# Schematic_Daughter_Board.net
KiCad netlist of a schematic drawn in Altium Designer
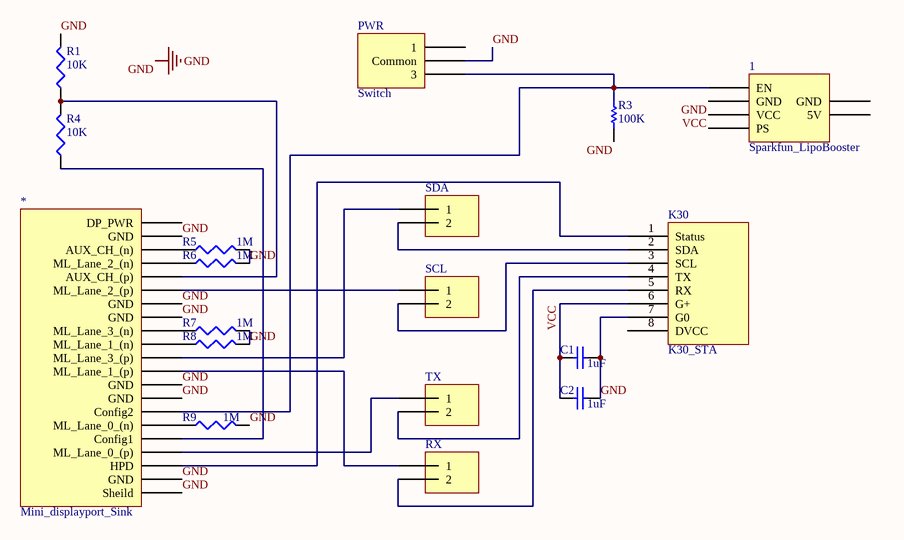
[diagram p0: Schematic_Daughter_Board.SchDoc]

(export (version "E")
  (design (tool "Eeschema 10.0.6"))
  (components
    (comp (ref "*")
      (value "Mini_displayport_Sink")
      (footprint "CONN_Displayport")
      (libsource (lib "Parts_Schematic") (part "Mini_displayport_Sink"))
    )
    (comp (ref "1")
      (value "Sparkfun_LipoBooster")
      (footprint "Sparkfun_lipoBooster")
      (libsource (lib "Schematic_Library_DaughterBoard") (part "Sparkfun_LipoBooster"))
    )
    (comp (ref "C1")
      (value "1uF")
      (footprint "C0805")
      (description "Capacitor (Semiconductor SIM Model)")
      (fields (field (name "Comment") "Cap Semi") (field (name "PUBLISHER") "Altium Limited"))
      (libsource (lib "Miscellaneous Devices") (part "Cap Semi"))
    )
    (comp (ref "C2")
      (value "1uF")
      (footprint "C0805")
      (description "Capacitor (Semiconductor SIM Model)")
      (fields (field (name "Comment") "Cap Semi") (field (name "PUBLISHER") "Altium Limited"))
      (libsource (lib "Miscellaneous Devices") (part "Cap Semi"))
    )
    (comp (ref "K30")
      (value "K30_STA")
      (footprint "K30_STA")
      (libsource (lib "Schematic_Library_DaughterBoard") (part "K30_STA"))
    )
    (comp (ref "PWR")
      (value "Switch")
      (footprint "Switch_footprint")
      (libsource (lib "Parts_Schematic") (part "Switch"))
    )
    (comp (ref "R1")
      (value "10K")
      (footprint "6-0805_N")
      (description "Resistor")
      (fields (field (name "Comment") "Res3") (field (name "PUBLISHER") "Altium Limited"))
      (libsource (lib "Miscellaneous Devices") (part "Res3"))
    )
    (comp (ref "R3")
      (value "100K")
      (footprint "AXIAL-0.3")
      (description "Resistor")
      (fields (field (name "Comment") "Res1") (field (name "PUBLISHER") "Altium Limited"))
      (libsource (lib "Miscellaneous Devices") (part "Res1"))
    )
    (comp (ref "R4")
      (value "10K")
      (footprint "6-0805_N")
      (description "Resistor")
      (fields (field (name "Comment") "Res3") (field (name "PUBLISHER") "Altium Limited"))
      (libsource (lib "Miscellaneous Devices") (part "Res3"))
    )
    (comp (ref "R5")
      (value "1M")
      (footprint "6-0805_N")
      (description "Resistor")
      (fields (field (name "Comment") "Res3") (field (name "PUBLISHER") "Altium Limited"))
      (libsource (lib "Miscellaneous Devices") (part "Res3"))
    )
    (comp (ref "R6")
      (value "1M")
      (footprint "6-0805_N")
      (description "Resistor")
      (fields (field (name "Comment") "Res3") (field (name "PUBLISHER") "Altium Limited"))
      (libsource (lib "Miscellaneous Devices") (part "Res3"))
    )
    (comp (ref "R7")
      (value "1M")
      (footprint "6-0805_N")
      (description "Resistor")
      (fields (field (name "Comment") "Res3") (field (name "PUBLISHER") "Altium Limited"))
      (libsource (lib "Miscellaneous Devices") (part "Res3"))
    )
    (comp (ref "R8")
      (value "1M")
      (footprint "6-0805_N")
      (description "Resistor")
      (fields (field (name "Comment") "Res3") (field (name "PUBLISHER") "Altium Limited"))
      (libsource (lib "Miscellaneous Devices") (part "Res3"))
    )
    (comp (ref "R9")
      (value "1M")
      (footprint "6-0805_N")
      (description "Resistor")
      (fields (field (name "Comment") "Res3") (field (name "PUBLISHER") "Altium Limited"))
      (libsource (lib "Miscellaneous Devices") (part "Res3"))
    )
    (comp (ref "RX")
      (value "Solder_Jumper")
      (footprint "Solder_Jumper_Footprint")
      (libsource (lib "Schematic_Library_DaughterBoard") (part "Solder_Jumper"))
    )
    (comp (ref "SCL")
      (value "Solder_Jumper")
      (footprint "Solder_Jumper_Footprint")
      (libsource (lib "Schematic_Library_DaughterBoard") (part "Solder_Jumper"))
    )
    (comp (ref "SDA")
      (value "Solder_Jumper")
      (footprint "Solder_Jumper_Footprint")
      (libsource (lib "Schematic_Library_DaughterBoard") (part "Solder_Jumper"))
    )
    (comp (ref "TX")
      (value "Solder_Jumper")
      (footprint "Solder_Jumper_Footprint")
      (libsource (lib "Schematic_Library_DaughterBoard") (part "Solder_Jumper"))
    )
  )
  (nets
    (net (code "1") (name "/VCC") (class "Default")
      (node (ref "1") (pin "3") (pinfunction "VCC_3") (pintype "passive"))
      (node (ref "C1") (pin "2") (pinfunction "2_2") (pintype "passive"))
      (node (ref "C2") (pin "2") (pinfunction "2_2") (pintype "passive"))
      (node (ref "K30") (pin "6") (pinfunction "G+_6") (pintype "passive"))
    )
    (net (code "2") (name "GND") (class "Default")
      (node (ref "*") (pin "0") (pinfunction "Sheild_0") (pintype "passive"))
      (node (ref "*") (pin "1") (pinfunction "GND_1") (pintype "passive"))
      (node (ref "*") (pin "13") (pinfunction "GND_13") (pintype "passive"))
      (node (ref "*") (pin "14") (pinfunction "GND_14") (pintype "passive"))
      (node (ref "*") (pin "19") (pinfunction "GND_19") (pintype "passive"))
      (node (ref "*") (pin "7") (pinfunction "GND_7") (pintype "passive"))
      (node (ref "*") (pin "8") (pinfunction "GND_8") (pintype "passive"))
      (node (ref "1") (pin "2") (pinfunction "GND_2") (pintype "passive"))
      (node (ref "C1") (pin "1") (pinfunction "1_1") (pintype "passive"))
      (node (ref "C2") (pin "1") (pinfunction "1_1") (pintype "passive"))
      (node (ref "K30") (pin "7") (pinfunction "G0_7") (pintype "passive"))
      (node (ref "PWR") (pin "2") (pinfunction "Common_2") (pintype "passive"))
      (node (ref "R1") (pin "2") (pinfunction "2_2") (pintype "passive"))
      (node (ref "R3") (pin "1") (pinfunction "1_1") (pintype "passive"))
      (node (ref "R5") (pin "2") (pinfunction "2_2") (pintype "passive"))
      (node (ref "R6") (pin "2") (pinfunction "2_2") (pintype "passive"))
      (node (ref "R7") (pin "2") (pinfunction "2_2") (pintype "passive"))
      (node (ref "R8") (pin "2") (pinfunction "2_2") (pintype "passive"))
      (node (ref "R9") (pin "2") (pinfunction "2_2") (pintype "passive"))
    )
    (net (code "3") (name "Net-(*-AUX_CH_(n))") (class "Default")
      (node (ref "*") (pin "18") (pinfunction "AUX_CH_(n)_18") (pintype "passive"))
      (node (ref "R5") (pin "1") (pinfunction "1_1") (pintype "passive"))
    )
    (net (code "4") (name "Net-(*-AUX_CH_(p))") (class "Default")
      (node (ref "*") (pin "16") (pinfunction "AUX_CH_(p)_16") (pintype "passive"))
      (node (ref "R1") (pin "1") (pinfunction "1_1") (pintype "passive"))
      (node (ref "R4") (pin "2") (pinfunction "2_2") (pintype "passive"))
    )
    (net (code "5") (name "Net-(*-Config1)") (class "Default")
      (node (ref "*") (pin "4") (pinfunction "Config1_4") (pintype "passive"))
      (node (ref "R4") (pin "1") (pinfunction "1_1") (pintype "passive"))
    )
    (net (code "6") (name "Net-(*-Config2)") (class "Default")
      (node (ref "*") (pin "6") (pinfunction "Config2_6") (pintype "passive"))
      (node (ref "1") (pin "1") (pinfunction "EN_1") (pintype "passive"))
      (node (ref "PWR") (pin "3") (pinfunction "3_3") (pintype "passive"))
      (node (ref "R3") (pin "2") (pinfunction "2_2") (pintype "passive"))
    )
    (net (code "7") (name "Net-(*-HPD)") (class "Default")
      (node (ref "*") (pin "2") (pinfunction "HPD_2") (pintype "passive"))
      (node (ref "K30") (pin "1") (pinfunction "Status_1") (pintype "passive"))
    )
    (net (code "8") (name "Net-(*-ML_Lane_0_(n))") (class "Default")
      (node (ref "*") (pin "10") (pinfunction "ML_Lane_0_(n)_10") (pintype "passive"))
      (node (ref "R9") (pin "1") (pinfunction "1_1") (pintype "passive"))
    )
    (net (code "9") (name "Net-(*-ML_Lane_0_(p))") (class "Default")
      (node (ref "*") (pin "12") (pinfunction "ML_Lane_0_(p)_12") (pintype "passive"))
      (node (ref "TX") (pin "1") (pinfunction "1_1") (pintype "passive"))
    )
    (net (code "10") (name "Net-(*-ML_Lane_1_(n))") (class "Default")
      (node (ref "*") (pin "15") (pinfunction "ML_Lane_1_(n)_15") (pintype "passive"))
      (node (ref "R8") (pin "1") (pinfunction "1_1") (pintype "passive"))
    )
    (net (code "11") (name "Net-(*-ML_Lane_1_(p))") (class "Default")
      (node (ref "*") (pin "17") (pinfunction "ML_Lane_1_(p)_17") (pintype "passive"))
      (node (ref "RX") (pin "1") (pinfunction "1_1") (pintype "passive"))
    )
    (net (code "12") (name "Net-(*-ML_Lane_2_(n))") (class "Default")
      (node (ref "*") (pin "9") (pinfunction "ML_Lane_2_(n)_9") (pintype "passive"))
      (node (ref "R6") (pin "1") (pinfunction "1_1") (pintype "passive"))
    )
    (net (code "13") (name "Net-(*-ML_Lane_2_(p))") (class "Default")
      (node (ref "*") (pin "11") (pinfunction "ML_Lane_2_(p)_11") (pintype "passive"))
      (node (ref "SCL") (pin "1") (pinfunction "1_1") (pintype "passive"))
    )
    (net (code "14") (name "Net-(*-ML_Lane_3_(n))") (class "Default")
      (node (ref "*") (pin "3") (pinfunction "ML_Lane_3_(n)_3") (pintype "passive"))
      (node (ref "R7") (pin "1") (pinfunction "1_1") (pintype "passive"))
    )
    (net (code "15") (name "Net-(*-ML_Lane_3_(p))") (class "Default")
      (node (ref "*") (pin "5") (pinfunction "ML_Lane_3_(p)_5") (pintype "passive"))
      (node (ref "SDA") (pin "1") (pinfunction "1_1") (pintype "passive"))
    )
    (net (code "16") (name "Net-(K30-RX)") (class "Default")
      (node (ref "K30") (pin "5") (pinfunction "RX_5") (pintype "passive"))
      (node (ref "RX") (pin "2") (pinfunction "2_2") (pintype "passive"))
    )
    (net (code "17") (name "Net-(K30-SCL)") (class "Default")
      (node (ref "K30") (pin "3") (pinfunction "SCL_3") (pintype "passive"))
      (node (ref "SCL") (pin "2") (pinfunction "2_2") (pintype "passive"))
    )
    (net (code "18") (name "Net-(K30-SDA)") (class "Default")
      (node (ref "K30") (pin "2") (pinfunction "SDA_2") (pintype "passive"))
      (node (ref "SDA") (pin "2") (pinfunction "2_2") (pintype "passive"))
    )
    (net (code "19") (name "Net-(K30-TX)") (class "Default")
      (node (ref "K30") (pin "4") (pinfunction "TX_4") (pintype "passive"))
      (node (ref "TX") (pin "2") (pinfunction "2_2") (pintype "passive"))
    )
    (net (code "20") (name "unconnected-(*-DP_PWR-Pad20)") (class "Default")
      (node (ref "*") (pin "20") (pinfunction "DP_PWR_20") (pintype "passive"))
    )
    (net (code "21") (name "unconnected-(1-5V-Pad5)") (class "Default")
      (node (ref "1") (pin "5") (pinfunction "5V_5") (pintype "passive"))
    )
    (net (code "22") (name "unconnected-(1-GND-Pad6)") (class "Default")
      (node (ref "1") (pin "6") (pinfunction "GND_6") (pintype "passive"))
    )
    (net (code "23") (name "unconnected-(1-PS-Pad4)") (class "Default")
      (node (ref "1") (pin "4") (pinfunction "PS_4") (pintype "passive"))
    )
    (net (code "24") (name "unconnected-(K30-DVCC-Pad8)") (class "Default")
      (node (ref "K30") (pin "8") (pinfunction "DVCC_8") (pintype "passive"))
    )
    (net (code "25") (name "unconnected-(PWR-Pad1)") (class "Default")
      (node (ref "PWR") (pin "1") (pinfunction "1_1") (pintype "passive"))
    )
  )
)
